# ProPrj_hackpod.net
KiCad netlist of a schematic drawn in EasyEDA Pro
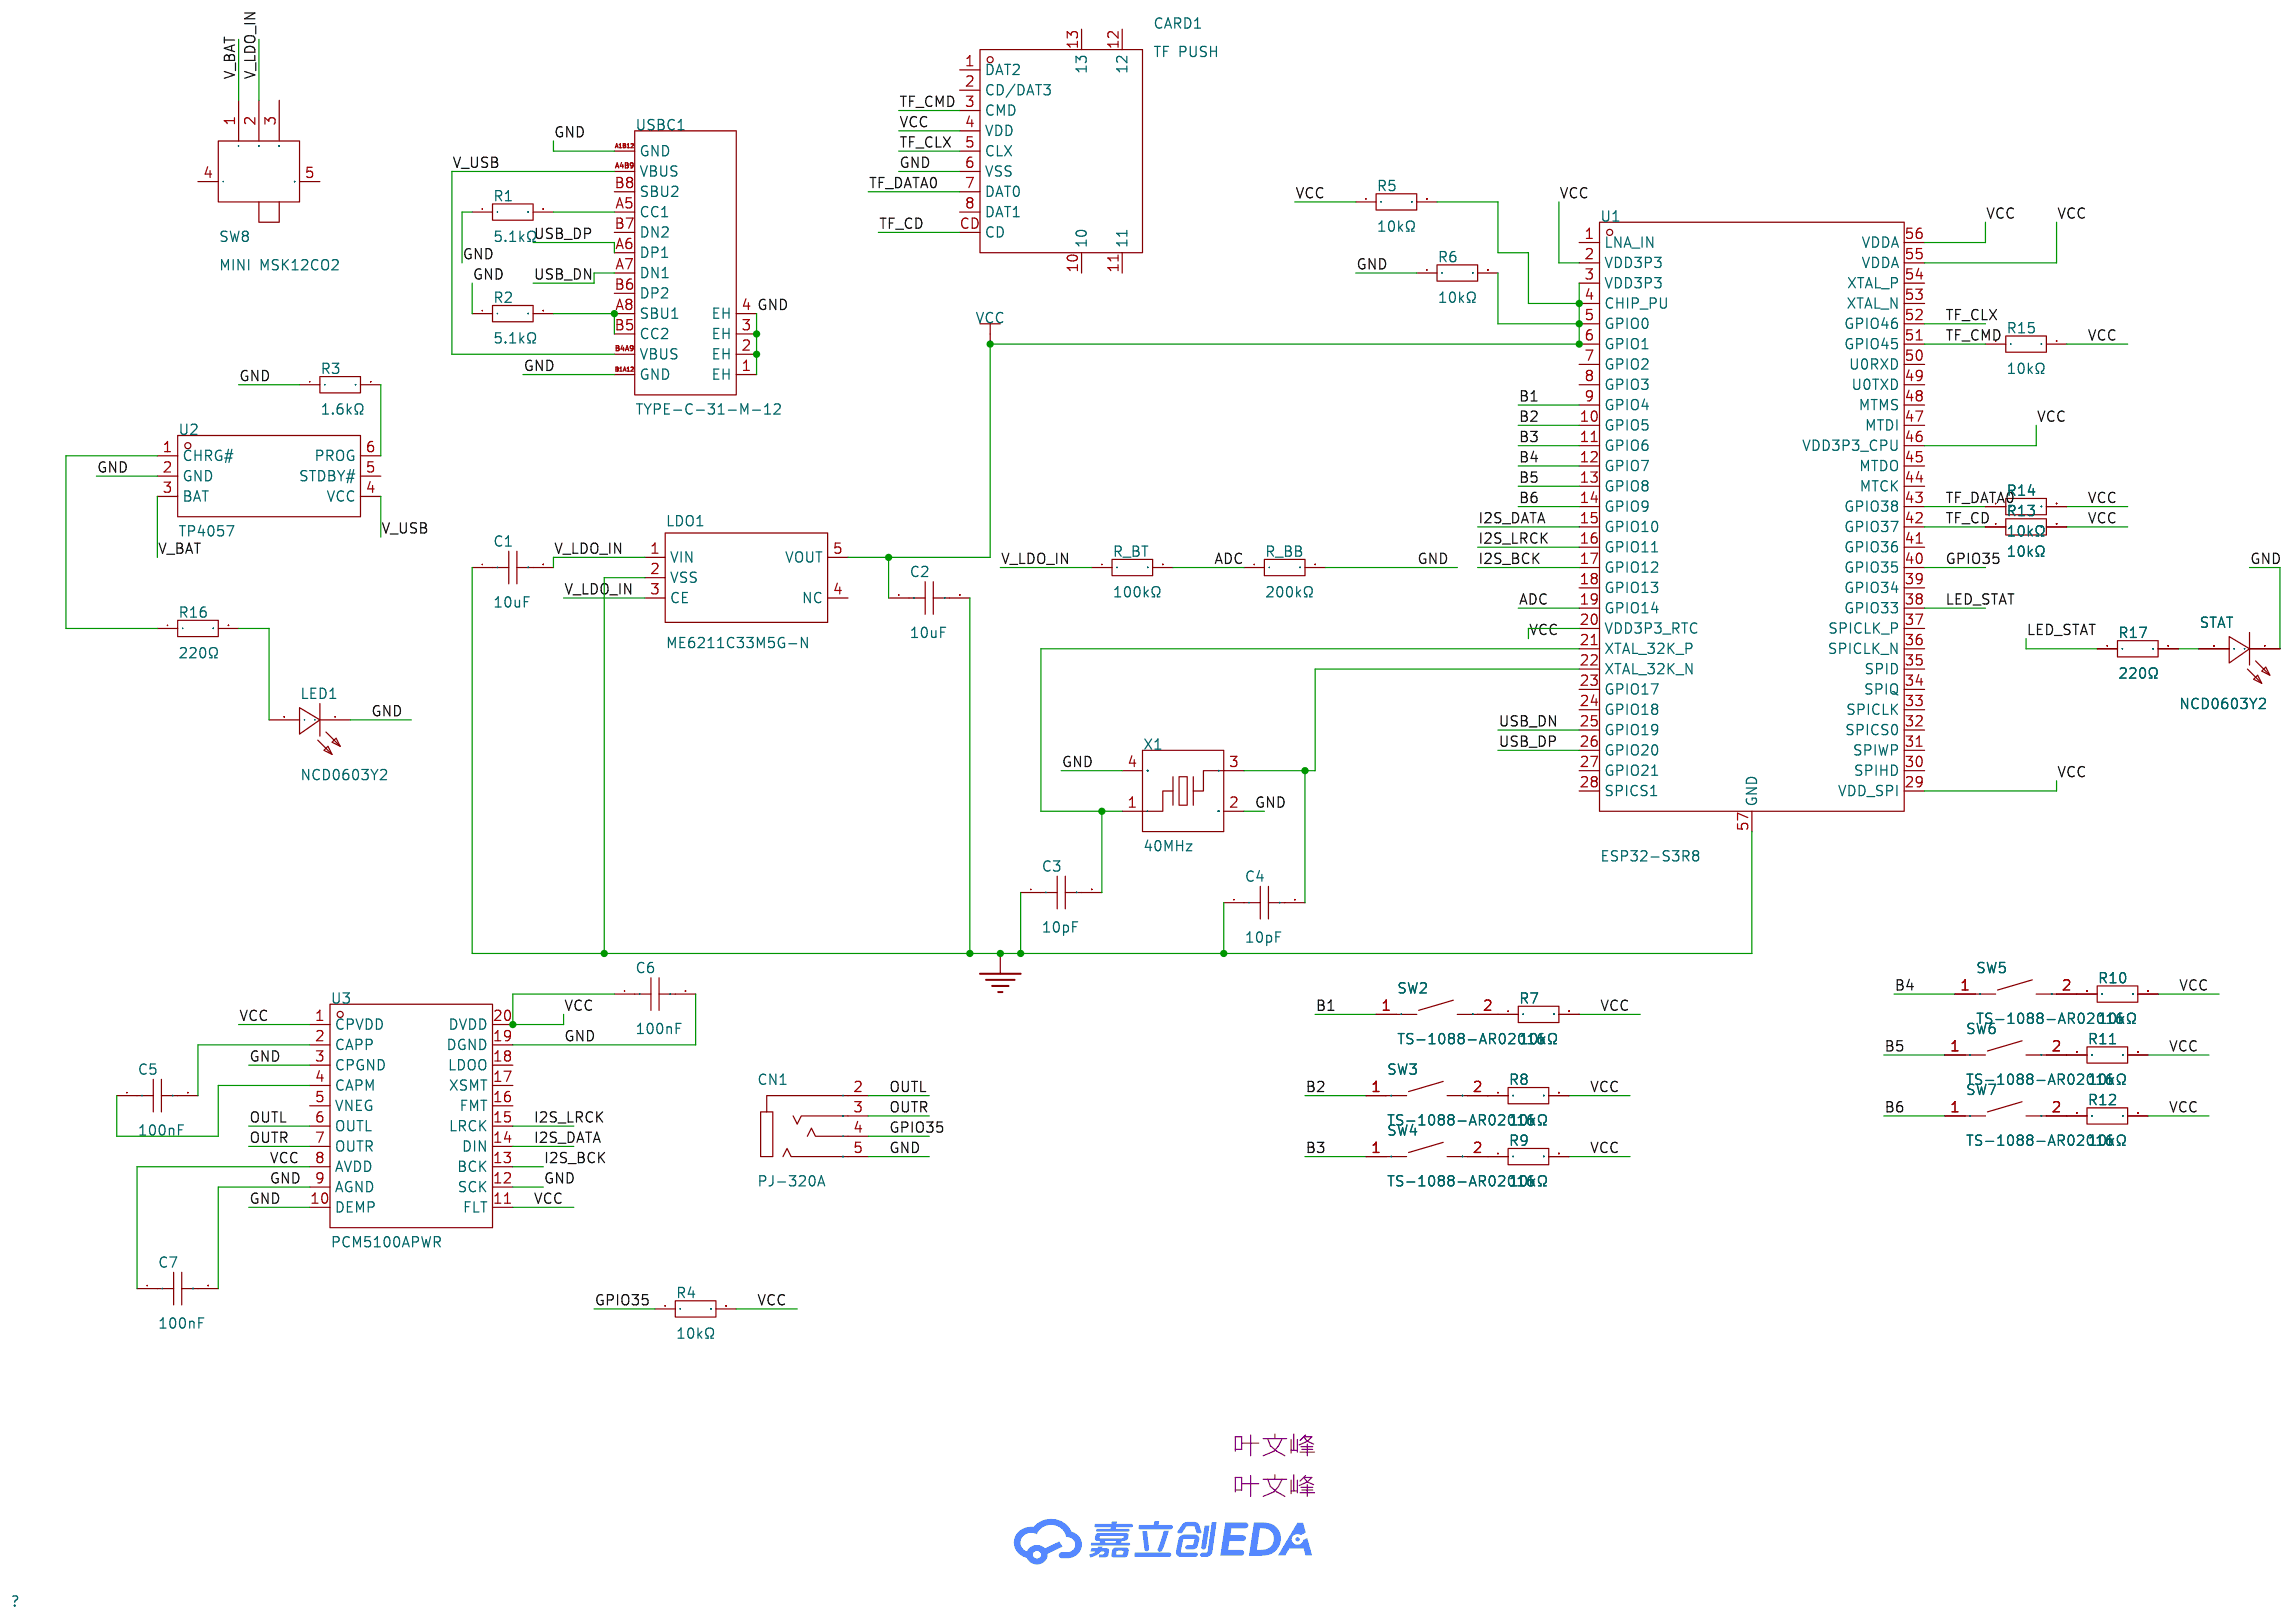
[diagram p0: schematic sheet]

(export (version "E")
  (design (tool "Eeschema 10.0.6"))
  (components
    (comp (ref "C1")
      (value "10uF")
      (footprint "easyedapro:C0603")
      (libsource (lib "easyedapro") (part "Capacitance"))
    )
    (comp (ref "C2")
      (value "10uF")
      (footprint "easyedapro:C0603")
      (libsource (lib "easyedapro") (part "Capacitance"))
    )
    (comp (ref "C3")
      (value "10pF")
      (footprint "easyedapro:C0603")
      (libsource (lib "easyedapro") (part "Capacitance"))
    )
    (comp (ref "C4")
      (value "10pF")
      (footprint "easyedapro:C0603")
      (libsource (lib "easyedapro") (part "Capacitance"))
    )
    (comp (ref "C5")
      (value "100nF")
      (footprint "easyedapro:C0603")
      (libsource (lib "easyedapro") (part "Capacitance"))
    )
    (comp (ref "C6")
      (value "100nF")
      (footprint "easyedapro:C0603")
      (libsource (lib "easyedapro") (part "Capacitance"))
    )
    (comp (ref "C7")
      (value "100nF")
      (footprint "easyedapro:C0603")
      (libsource (lib "easyedapro") (part "Capacitance"))
    )
    (comp (ref "CARD1")
      (value "TF PUSH")
      (footprint "easyedapro:TF-SMD_TF-PUSH")
      (description "卡连接方式:自弹式;卡类型:MicroSD卡(TF卡);连接器类型:卡座;本体最大高度:2mm;工作温度:-25°C~+90°C;")
      (fields (field (name "Manufacturer") "SHOU HAN(首韩)"))
      (libsource (lib "easyedapro") (part "TF PUSH"))
    )
    (comp (ref "CN1")
      (value "PJ-320A")
      (footprint "easyedapro:AUDIO-TH_PJ-320A_C49284721")
      (description "连接器类型:3.5mm耳机座;额定电流:500mA;额定电压:30V;触头材质:铜;触头镀层:金;工作温度:-25°C~+85°C;")
      (fields (field (name "Manufacturer") "XUNPU(讯普)"))
      (libsource (lib "easyedapro") (part "PJ-320A_C49284721"))
    )
    (comp (ref "LDO1")
      (value "ME6211C33M5G-N")
      (footprint "easyedapro:SOT-23-5_L3.0-W1.7-P0.95-LS2.8-BL")
      (description "输出类型:固定;工作电压:6V;输出电压:3.3V;输出电流:500mA;电源纹波抑制比(PSRR):70dB@(1kHz);输出极性:正极;")
      (fields (field (name "Manufacturer") "MICRONE(南京微盟)"))
      (libsource (lib "easyedapro") (part "ME6211C33M5G-N"))
    )
    (comp (ref "LED1")
      (value "NCD0603Y2")
      (footprint "easyedapro:LED0603-RD")
      (fields (field (name "Manufacturer") "国星光电"))
      (libsource (lib "easyedapro") (part "FC-1608YXK-585F08"))
    )
    (comp (ref "R1")
      (value "5.1kΩ")
      (footprint "easyedapro:R0603")
      (libsource (lib "easyedapro") (part "电阻"))
    )
    (comp (ref "R2")
      (value "5.1kΩ")
      (footprint "easyedapro:R0603")
      (libsource (lib "easyedapro") (part "电阻"))
    )
    (comp (ref "R3")
      (value "1.6kΩ")
      (footprint "easyedapro:R0603")
      (libsource (lib "easyedapro") (part "电阻"))
    )
    (comp (ref "R4") (value "10kΩ") (footprint "easyedapro:R0603") (libsource (lib "easyedapro") (part "电阻")))
    (comp (ref "R5") (value "10kΩ") (footprint "easyedapro:R0603") (libsource (lib "easyedapro") (part "电阻")))
    (comp (ref "R6") (value "10kΩ") (footprint "easyedapro:R0603") (libsource (lib "easyedapro") (part "电阻")))
    (comp (ref "R7") (value "10kΩ") (footprint "easyedapro:R0603") (libsource (lib "easyedapro") (part "电阻")))
    (comp (ref "R8") (value "10kΩ") (footprint "easyedapro:R0603") (libsource (lib "easyedapro") (part "电阻")))
    (comp (ref "R9") (value "10kΩ") (footprint "easyedapro:R0603") (libsource (lib "easyedapro") (part "电阻")))
    (comp (ref "R10")
      (value "10kΩ")
      (footprint "easyedapro:R0603")
      (libsource (lib "easyedapro") (part "电阻"))
    )
    (comp (ref "R11")
      (value "10kΩ")
      (footprint "easyedapro:R0603")
      (libsource (lib "easyedapro") (part "电阻"))
    )
    (comp (ref "R12")
      (value "10kΩ")
      (footprint "easyedapro:R0603")
      (libsource (lib "easyedapro") (part "电阻"))
    )
    (comp (ref "R13")
      (value "10kΩ")
      (footprint "easyedapro:R0603")
      (libsource (lib "easyedapro") (part "电阻"))
    )
    (comp (ref "R14")
      (value "10kΩ")
      (footprint "easyedapro:R0603")
      (libsource (lib "easyedapro") (part "电阻"))
    )
    (comp (ref "R15")
      (value "10kΩ")
      (footprint "easyedapro:R0603")
      (libsource (lib "easyedapro") (part "电阻"))
    )
    (comp (ref "R16")
      (value "220Ω")
      (footprint "easyedapro:R0603")
      (libsource (lib "easyedapro") (part "电阻"))
    )
    (comp (ref "R17")
      (value "220Ω")
      (footprint "easyedapro:R0603")
      (fields (field (name "Manufacturer Part") "FRC0603J221 TS") (field (name "Manufacturer") "FOJAN(富捷)"))
      (libsource (lib "easyedapro") (part "电阻"))
    )
    (comp (ref "R_BB")
      (value "200kΩ")
      (footprint "easyedapro:R0603")
      (fields (field (name "Manufacturer Part") "ERA3AEB204V") (field (name "Manufacturer") "PANASONIC(松下)"))
      (libsource (lib "easyedapro") (part "电阻"))
    )
    (comp (ref "R_BT")
      (value "100kΩ")
      (footprint "easyedapro:R0603")
      (fields (field (name "Manufacturer Part") "ERJ3EKF1003V") (field (name "Manufacturer") "PANASONIC(松下)"))
      (libsource (lib "easyedapro") (part "电阻"))
    )
    (comp (ref "STAT")
      (value "NCD0603Y2")
      (footprint "easyedapro:LED0603-RD")
      (fields (field (name "Manufacturer") "国星光电"))
      (libsource (lib "easyedapro") (part "FC-1608YXK-585F08"))
    )
    (comp (ref "SW2")
      (value "TS-1088-AR02016")
      (footprint "easyedapro:SW-SMD_L3.9-W3.0-P4.45")
      (fields (field (name "Manufacturer") "XUNPU(讯普)"))
      (libsource (lib "easyedapro") (part "TS-1088-AR02016"))
    )
    (comp (ref "SW3")
      (value "TS-1088-AR02016")
      (footprint "easyedapro:SW-SMD_L3.9-W3.0-P4.45")
      (fields (field (name "Manufacturer") "XUNPU(讯普)"))
      (libsource (lib "easyedapro") (part "TS-1088-AR02016"))
    )
    (comp (ref "SW4")
      (value "TS-1088-AR02016")
      (footprint "easyedapro:SW-SMD_L3.9-W3.0-P4.45")
      (fields (field (name "Manufacturer") "XUNPU(讯普)"))
      (libsource (lib "easyedapro") (part "TS-1088-AR02016"))
    )
    (comp (ref "SW5")
      (value "TS-1088-AR02016")
      (footprint "easyedapro:SW-SMD_L3.9-W3.0-P4.45")
      (fields (field (name "Manufacturer") "XUNPU(讯普)"))
      (libsource (lib "easyedapro") (part "TS-1088-AR02016"))
    )
    (comp (ref "SW6")
      (value "TS-1088-AR02016")
      (footprint "easyedapro:SW-SMD_L3.9-W3.0-P4.45")
      (fields (field (name "Manufacturer") "XUNPU(讯普)"))
      (libsource (lib "easyedapro") (part "TS-1088-AR02016"))
    )
    (comp (ref "SW7")
      (value "TS-1088-AR02016")
      (footprint "easyedapro:SW-SMD_L3.9-W3.0-P4.45")
      (fields (field (name "Manufacturer") "XUNPU(讯普)"))
      (libsource (lib "easyedapro") (part "TS-1088-AR02016"))
    )
    (comp (ref "SW8")
      (value "MINI MSK12CO2")
      (footprint "easyedapro:SW-SMD_MSK12CO2")
      (description "电路结构:单刀双掷;安装方式:卧贴;开关颜色:白色;额定电流:50mA;额定电压:12V;工作寿命:1万次;")
      (fields (field (name "Manufacturer") "SHOU HAN(首韩)"))
      (libsource (lib "easyedapro") (part "MINI MSK12CO2"))
    )
    (comp (ref "U1")
      (value "ESP32-S3R8")
      (footprint "easyedapro:QFN-56_L7.0-W7.0-P0.40-TL-EP4.0")
      (fields (field (name "Manufacturer") "ESPRESSIF(乐鑫)"))
      (libsource (lib "easyedapro") (part "ESP32-S3(R8)"))
    )
    (comp (ref "U2")
      (value "TP4057")
      (footprint "easyedapro:SOT-23-6_L2.9-W1.6-P0.95-LS2.8-BR")
      (description "工作电压:4V~6.5V;最大充电电流:500mA;电池类型:锂离子;电池节数:1;")
      (fields (field (name "Manufacturer") "UMW(友台半导体)"))
      (libsource (lib "easyedapro") (part "TP4057_C725791"))
    )
    (comp (ref "U3")
      (value "PCM5100APWR")
      (footprint "easyedapro:TSSOP-20_L6.5-W4.4-P0.65-LS6.4-BL")
      (description "工作电压:1.8V~3.3V;接口类型:I2S;")
      (fields (field (name "Manufacturer") "TI(德州仪器)"))
      (libsource (lib "easyedapro") (part "PCM5100APWR"))
    )
    (comp (ref "USBC1")
      (value "TYPE-C-31-M-12")
      (footprint "easyedapro:USB-C_SMD-TYPE-C-31-M-12_1")
      (description "连接器类型:Type-C;协议标准:-;公母:母;安装方式:-;触点数量:16P;端口数量:1;额定电流 - 电源:5A;工作温度:-;")
      (fields (field (name "Manufacturer") "韩国韩荣"))
      (libsource (lib "easyedapro") (part "TYPE-C-31-M-12"))
    )
    (comp (ref "X1")
      (value "40MHz")
      (footprint "easyedapro:CRYSTAL-SMD_4P-L3.2-W2.5-BL")
      (description "晶振类型:贴片晶振;频率:40MHz;常温频差:±10ppm;负载电容:15pF;频率稳定度:±20ppm;")
      (fields
        (field (name "Manufacturer Part") "XL2EL89CPI-111YLC-40M")
        (field (name "Manufacturer") "YXC(扬兴晶振)")
      )
      (libsource (lib "easyedapro") (part "XL2EL89CPI-111YLC-40M"))
    )
  )
  (nets
    (net (code "1") (name "/ADC") (class "Default")
      (node (ref "R_BB") (pin "1") (pinfunction "1_1") (pintype "input"))
      (node (ref "R_BT") (pin "2") (pinfunction "2_2") (pintype "input"))
      (node (ref "U1") (pin "19") (pinfunction "GPIO14_19") (pintype "unspecified"))
    )
    (net (code "2") (name "/B1") (class "Default")
      (node (ref "SW2") (pin "1") (pinfunction "1_1") (pintype "unspecified"))
      (node (ref "U1") (pin "9") (pinfunction "GPIO4_9") (pintype "unspecified"))
    )
    (net (code "3") (name "/B2") (class "Default")
      (node (ref "SW3") (pin "1") (pinfunction "1_1") (pintype "unspecified"))
      (node (ref "U1") (pin "10") (pinfunction "GPIO5_10") (pintype "unspecified"))
    )
    (net (code "4") (name "/B3") (class "Default")
      (node (ref "SW4") (pin "1") (pinfunction "1_1") (pintype "unspecified"))
      (node (ref "U1") (pin "11") (pinfunction "GPIO6_11") (pintype "unspecified"))
    )
    (net (code "5") (name "/B4") (class "Default")
      (node (ref "SW5") (pin "1") (pinfunction "1_1") (pintype "unspecified"))
      (node (ref "U1") (pin "12") (pinfunction "GPIO7_12") (pintype "unspecified"))
    )
    (net (code "6") (name "/B5") (class "Default")
      (node (ref "SW6") (pin "1") (pinfunction "1_1") (pintype "unspecified"))
      (node (ref "U1") (pin "13") (pinfunction "GPIO8_13") (pintype "unspecified"))
    )
    (net (code "7") (name "/B6") (class "Default")
      (node (ref "SW7") (pin "1") (pinfunction "1_1") (pintype "unspecified"))
      (node (ref "U1") (pin "14") (pinfunction "GPIO9_14") (pintype "unspecified"))
    )
    (net (code "8") (name "/GPIO35") (class "Default")
      (node (ref "CN1") (pin "4") (pinfunction "4_4") (pintype "unspecified"))
      (node (ref "R4") (pin "1") (pinfunction "1_1") (pintype "input"))
      (node (ref "U1") (pin "40") (pinfunction "GPIO35_40") (pintype "unspecified"))
    )
    (net (code "9") (name "/I2S_BCK") (class "Default")
      (node (ref "U1") (pin "17") (pinfunction "GPIO12_17") (pintype "unspecified"))
      (node (ref "U3") (pin "13") (pinfunction "BCK_13") (pintype "unspecified"))
    )
    (net (code "10") (name "/I2S_DATA") (class "Default")
      (node (ref "U1") (pin "15") (pinfunction "GPIO10_15") (pintype "unspecified"))
      (node (ref "U3") (pin "14") (pinfunction "DIN_14") (pintype "unspecified"))
    )
    (net (code "11") (name "/I2S_LRCK") (class "Default")
      (node (ref "U1") (pin "16") (pinfunction "GPIO11_16") (pintype "unspecified"))
      (node (ref "U3") (pin "15") (pinfunction "LRCK_15") (pintype "unspecified"))
    )
    (net (code "12") (name "/LED_STAT") (class "Default")
      (node (ref "R17") (pin "1") (pinfunction "1_1") (pintype "input"))
      (node (ref "U1") (pin "38") (pinfunction "GPIO33_38") (pintype "unspecified"))
    )
    (net (code "13") (name "/OUTL") (class "Default")
      (node (ref "CN1") (pin "2") (pinfunction "2_2") (pintype "unspecified"))
      (node (ref "U3") (pin "6") (pinfunction "OUTL_6") (pintype "unspecified"))
    )
    (net (code "14") (name "/OUTR") (class "Default")
      (node (ref "CN1") (pin "3") (pinfunction "3_3") (pintype "unspecified"))
      (node (ref "U3") (pin "7") (pinfunction "OUTR_7") (pintype "unspecified"))
    )
    (net (code "15") (name "/TF_CD") (class "Default")
      (node (ref "CARD1") (pin "CD") (pinfunction "CD_CD") (pintype "unspecified"))
      (node (ref "R13") (pin "1") (pinfunction "1_1") (pintype "input"))
      (node (ref "U1") (pin "42") (pinfunction "GPIO37_42") (pintype "unspecified"))
    )
    (net (code "16") (name "/TF_CLX") (class "Default")
      (node (ref "CARD1") (pin "5") (pinfunction "CLX_5") (pintype "unspecified"))
      (node (ref "U1") (pin "52") (pinfunction "GPIO46_52") (pintype "unspecified"))
    )
    (net (code "17") (name "/TF_CMD") (class "Default")
      (node (ref "CARD1") (pin "3") (pinfunction "CMD_3") (pintype "unspecified"))
      (node (ref "R15") (pin "1") (pinfunction "1_1") (pintype "input"))
      (node (ref "U1") (pin "51") (pinfunction "GPIO45_51") (pintype "unspecified"))
    )
    (net (code "18") (name "/TF_DATA0") (class "Default")
      (node (ref "CARD1") (pin "7") (pinfunction "DAT0_7") (pintype "unspecified"))
      (node (ref "R14") (pin "1") (pinfunction "1_1") (pintype "input"))
      (node (ref "U1") (pin "43") (pinfunction "GPIO38_43") (pintype "unspecified"))
    )
    (net (code "19") (name "/USB_DN") (class "Default")
      (node (ref "U1") (pin "25") (pinfunction "GPIO19_25") (pintype "unspecified"))
      (node (ref "USBC1") (pin "A7") (pinfunction "DN1_A7") (pintype "unspecified"))
    )
    (net (code "20") (name "/USB_DP") (class "Default")
      (node (ref "U1") (pin "26") (pinfunction "GPIO20_26") (pintype "unspecified"))
      (node (ref "USBC1") (pin "A6") (pinfunction "DP1_A6") (pintype "unspecified"))
    )
    (net (code "21") (name "/V_BAT") (class "Default")
      (node (ref "SW8") (pin "1") (pinfunction "1_1") (pintype "unspecified"))
      (node (ref "U2") (pin "3") (pinfunction "BAT_3") (pintype "unspecified"))
    )
    (net (code "22") (name "/V_LDO_IN") (class "Default")
      (node (ref "C1") (pin "2") (pinfunction "2_2") (pintype "input"))
      (node (ref "LDO1") (pin "1") (pinfunction "VIN_1") (pintype "unspecified"))
      (node (ref "LDO1") (pin "3") (pinfunction "CE_3") (pintype "unspecified"))
      (node (ref "R_BT") (pin "1") (pinfunction "1_1") (pintype "input"))
      (node (ref "SW8") (pin "2") (pinfunction "2_2") (pintype "unspecified"))
    )
    (net (code "23") (name "/V_USB") (class "Default")
      (node (ref "U2") (pin "4") (pinfunction "VCC_4") (pintype "unspecified"))
      (node (ref "USBC1") (pin "A4B9") (pinfunction "VBUS_A4B9") (pintype "unspecified"))
      (node (ref "USBC1") (pin "B4A9") (pinfunction "VBUS_B4A9") (pintype "unspecified"))
    )
    (net (code "24") (name "GND") (class "Default")
      (node (ref "C1") (pin "1") (pinfunction "1_1") (pintype "input"))
      (node (ref "C2") (pin "2") (pinfunction "2_2") (pintype "input"))
      (node (ref "C3") (pin "1") (pinfunction "1_1") (pintype "input"))
      (node (ref "C4") (pin "1") (pinfunction "1_1") (pintype "input"))
      (node (ref "C6") (pin "2") (pinfunction "2_2") (pintype "input"))
      (node (ref "C7") (pin "2") (pinfunction "2_2") (pintype "input"))
      (node (ref "CARD1") (pin "6") (pinfunction "VSS_6") (pintype "unspecified"))
      (node (ref "CN1") (pin "5") (pinfunction "5_5") (pintype "unspecified"))
      (node (ref "LDO1") (pin "2") (pinfunction "VSS_2") (pintype "unspecified"))
      (node (ref "LED1") (pin "1") (pinfunction "K_1") (pintype "unspecified"))
      (node (ref "R1") (pin "1") (pinfunction "1_1") (pintype "input"))
      (node (ref "R2") (pin "1") (pinfunction "1_1") (pintype "input"))
      (node (ref "R3") (pin "1") (pinfunction "1_1") (pintype "input"))
      (node (ref "R6") (pin "1") (pinfunction "1_1") (pintype "input"))
      (node (ref "R_BB") (pin "2") (pinfunction "2_2") (pintype "input"))
      (node (ref "STAT") (pin "1") (pinfunction "K_1") (pintype "unspecified"))
      (node (ref "U1") (pin "57") (pinfunction "GND_57") (pintype "unspecified"))
      (node (ref "U2") (pin "2") (pinfunction "GND_2") (pintype "unspecified"))
      (node (ref "U3") (pin "10") (pinfunction "DEMP_10") (pintype "unspecified"))
      (node (ref "U3") (pin "12") (pinfunction "SCK_12") (pintype "unspecified"))
      (node (ref "U3") (pin "19") (pinfunction "DGND_19") (pintype "unspecified"))
      (node (ref "U3") (pin "3") (pinfunction "CPGND_3") (pintype "unspecified"))
      (node (ref "U3") (pin "9") (pinfunction "AGND_9") (pintype "unspecified"))
      (node (ref "USBC1") (pin "1") (pinfunction "EH_1") (pintype "unspecified"))
      (node (ref "USBC1") (pin "2") (pinfunction "EH_2") (pintype "unspecified"))
      (node (ref "USBC1") (pin "3") (pinfunction "EH_3") (pintype "unspecified"))
      (node (ref "USBC1") (pin "4") (pinfunction "EH_4") (pintype "unspecified"))
      (node (ref "USBC1") (pin "A1B12") (pinfunction "GND_A1B12") (pintype "unspecified"))
      (node (ref "USBC1") (pin "B1A12") (pinfunction "GND_B1A12") (pintype "unspecified"))
      (node (ref "X1") (pin "2") (pinfunction "GND_2") (pintype "input"))
      (node (ref "X1") (pin "4") (pinfunction "GND_4") (pintype "input"))
    )
    (net (code "25") (name "Net-(LED1-A)") (class "Default")
      (node (ref "LED1") (pin "2") (pinfunction "A_2") (pintype "unspecified"))
      (node (ref "R16") (pin "2") (pinfunction "2_2") (pintype "input"))
    )
    (net (code "26") (name "Net-(R7-Pad1)") (class "Default")
      (node (ref "R7") (pin "1") (pinfunction "1_1") (pintype "input"))
      (node (ref "SW2") (pin "2") (pinfunction "2_2") (pintype "unspecified"))
    )
    (net (code "27") (name "Net-(R8-Pad1)") (class "Default")
      (node (ref "R8") (pin "1") (pinfunction "1_1") (pintype "input"))
      (node (ref "SW3") (pin "2") (pinfunction "2_2") (pintype "unspecified"))
    )
    (net (code "28") (name "Net-(R9-Pad1)") (class "Default")
      (node (ref "R9") (pin "1") (pinfunction "1_1") (pintype "input"))
      (node (ref "SW4") (pin "2") (pinfunction "2_2") (pintype "unspecified"))
    )
    (net (code "29") (name "Net-(R10-Pad1)") (class "Default")
      (node (ref "R10") (pin "1") (pinfunction "1_1") (pintype "input"))
      (node (ref "SW5") (pin "2") (pinfunction "2_2") (pintype "unspecified"))
    )
    (net (code "30") (name "Net-(R11-Pad1)") (class "Default")
      (node (ref "R11") (pin "1") (pinfunction "1_1") (pintype "input"))
      (node (ref "SW6") (pin "2") (pinfunction "2_2") (pintype "unspecified"))
    )
    (net (code "31") (name "Net-(R12-Pad1)") (class "Default")
      (node (ref "R12") (pin "1") (pinfunction "1_1") (pintype "input"))
      (node (ref "SW7") (pin "2") (pinfunction "2_2") (pintype "unspecified"))
    )
    (net (code "32") (name "Net-(STAT-A)") (class "Default")
      (node (ref "R17") (pin "2") (pinfunction "2_2") (pintype "input"))
      (node (ref "STAT") (pin "2") (pinfunction "A_2") (pintype "unspecified"))
    )
    (net (code "33") (name "Net-(U1-XTAL_32K_N)") (class "Default")
      (node (ref "C4") (pin "2") (pinfunction "2_2") (pintype "input"))
      (node (ref "U1") (pin "22") (pinfunction "XTAL_32K_N_22") (pintype "unspecified"))
      (node (ref "X1") (pin "3") (pinfunction "3_3") (pintype "input"))
    )
    (net (code "34") (name "Net-(U1-XTAL_32K_P)") (class "Default")
      (node (ref "C3") (pin "2") (pinfunction "2_2") (pintype "input"))
      (node (ref "U1") (pin "21") (pinfunction "XTAL_32K_P_21") (pintype "unspecified"))
      (node (ref "X1") (pin "1") (pinfunction "1_1") (pintype "input"))
    )
    (net (code "35") (name "Net-(U2-CHRG#)") (class "Default")
      (node (ref "R16") (pin "1") (pinfunction "1_1") (pintype "input"))
      (node (ref "U2") (pin "1") (pinfunction "CHRG#_1") (pintype "unspecified"))
    )
    (net (code "36") (name "Net-(U2-PROG)") (class "Default")
      (node (ref "R3") (pin "2") (pinfunction "2_2") (pintype "input"))
      (node (ref "U2") (pin "6") (pinfunction "PROG_6") (pintype "unspecified"))
    )
    (net (code "37") (name "Net-(U3-CAPM)") (class "Default")
      (node (ref "C5") (pin "1") (pinfunction "1_1") (pintype "input"))
      (node (ref "U3") (pin "4") (pinfunction "CAPM_4") (pintype "unspecified"))
    )
    (net (code "38") (name "Net-(U3-CAPP)") (class "Default")
      (node (ref "C5") (pin "2") (pinfunction "2_2") (pintype "input"))
      (node (ref "U3") (pin "2") (pinfunction "CAPP_2") (pintype "unspecified"))
    )
    (net (code "39") (name "Net-(USBC1-CC1)") (class "Default")
      (node (ref "R1") (pin "2") (pinfunction "2_2") (pintype "input"))
      (node (ref "USBC1") (pin "A5") (pinfunction "CC1_A5") (pintype "unspecified"))
    )
    (net (code "40") (name "Net-(USBC1-CC2)") (class "Default")
      (node (ref "R2") (pin "2") (pinfunction "2_2") (pintype "input"))
      (node (ref "USBC1") (pin "A8") (pinfunction "SBU1_A8") (pintype "unspecified"))
      (node (ref "USBC1") (pin "B5") (pinfunction "CC2_B5") (pintype "unspecified"))
    )
    (net (code "41") (name "VCC") (class "Default")
      (node (ref "C2") (pin "1") (pinfunction "1_1") (pintype "input"))
      (node (ref "C6") (pin "1") (pinfunction "1_1") (pintype "input"))
      (node (ref "C7") (pin "1") (pinfunction "1_1") (pintype "input"))
      (node (ref "CARD1") (pin "4") (pinfunction "VDD_4") (pintype "unspecified"))
      (node (ref "LDO1") (pin "5") (pinfunction "VOUT_5") (pintype "unspecified"))
      (node (ref "R10") (pin "2") (pinfunction "2_2") (pintype "input"))
      (node (ref "R11") (pin "2") (pinfunction "2_2") (pintype "input"))
      (node (ref "R12") (pin "2") (pinfunction "2_2") (pintype "input"))
      (node (ref "R13") (pin "2") (pinfunction "2_2") (pintype "input"))
      (node (ref "R14") (pin "2") (pinfunction "2_2") (pintype "input"))
      (node (ref "R15") (pin "2") (pinfunction "2_2") (pintype "input"))
      (node (ref "R4") (pin "2") (pinfunction "2_2") (pintype "input"))
      (node (ref "R5") (pin "1") (pinfunction "1_1") (pintype "input"))
      (node (ref "R5") (pin "2") (pinfunction "2_2") (pintype "input"))
      (node (ref "R6") (pin "2") (pinfunction "2_2") (pintype "input"))
      (node (ref "R7") (pin "2") (pinfunction "2_2") (pintype "input"))
      (node (ref "R8") (pin "2") (pinfunction "2_2") (pintype "input"))
      (node (ref "R9") (pin "2") (pinfunction "2_2") (pintype "input"))
      (node (ref "U1") (pin "2") (pinfunction "VDD3P3_2") (pintype "unspecified"))
      (node (ref "U1") (pin "20") (pinfunction "VDD3P3_RTC_20") (pintype "unspecified"))
      (node (ref "U1") (pin "29") (pinfunction "VDD_SPI_29") (pintype "unspecified"))
      (node (ref "U1") (pin "3") (pinfunction "VDD3P3_3") (pintype "unspecified"))
      (node (ref "U1") (pin "4") (pinfunction "CHIP_PU_4") (pintype "unspecified"))
      (node (ref "U1") (pin "46") (pinfunction "VDD3P3_CPU_46") (pintype "unspecified"))
      (node (ref "U1") (pin "5") (pinfunction "GPIO0_5") (pintype "unspecified"))
      (node (ref "U1") (pin "55") (pinfunction "VDDA_55") (pintype "unspecified"))
      (node (ref "U1") (pin "56") (pinfunction "VDDA_56") (pintype "unspecified"))
      (node (ref "U1") (pin "6") (pinfunction "GPIO1_6") (pintype "unspecified"))
      (node (ref "U3") (pin "1") (pinfunction "CPVDD_1") (pintype "unspecified"))
      (node (ref "U3") (pin "11") (pinfunction "FLT_11") (pintype "unspecified"))
      (node (ref "U3") (pin "20") (pinfunction "DVDD_20") (pintype "unspecified"))
      (node (ref "U3") (pin "8") (pinfunction "AVDD_8") (pintype "unspecified"))
    )
    (net (code "42") (name "unconnected-(CARD1-CD{slash}DAT3-Pad2)") (class "Default")
      (node (ref "CARD1") (pin "2") (pinfunction "CD/DAT3_2") (pintype "unspecified"))
    )
    (net (code "43") (name "unconnected-(CARD1-DAT1-Pad8)") (class "Default")
      (node (ref "CARD1") (pin "8") (pinfunction "DAT1_8") (pintype "unspecified"))
    )
    (net (code "44") (name "unconnected-(CARD1-DAT2-Pad1)") (class "Default")
      (node (ref "CARD1") (pin "1") (pinfunction "DAT2_1") (pintype "unspecified"))
    )
    (net (code "45") (name "unconnected-(CARD1-Pad10)") (class "Default")
      (node (ref "CARD1") (pin "10") (pinfunction "10_10") (pintype "unspecified"))
    )
    (net (code "46") (name "unconnected-(CARD1-Pad11)") (class "Default")
      (node (ref "CARD1") (pin "11") (pinfunction "11_11") (pintype "unspecified"))
    )
    (net (code "47") (name "unconnected-(CARD1-Pad12)") (class "Default")
      (node (ref "CARD1") (pin "12") (pinfunction "12_12") (pintype "unspecified"))
    )
    (net (code "48") (name "unconnected-(CARD1-Pad13)") (class "Default")
      (node (ref "CARD1") (pin "13") (pinfunction "13_13") (pintype "unspecified"))
    )
    (net (code "49") (name "unconnected-(LDO1-NC-Pad4)") (class "Default")
      (node (ref "LDO1") (pin "4") (pinfunction "NC_4") (pintype "unspecified"))
    )
    (net (code "50") (name "unconnected-(SW8-Pad3)") (class "Default")
      (node (ref "SW8") (pin "3") (pinfunction "3_3") (pintype "unspecified"))
    )
    (net (code "51") (name "unconnected-(SW8-Pad4)") (class "Default")
      (node (ref "SW8") (pin "4") (pinfunction "4_4") (pintype "unspecified"))
    )
    (net (code "52") (name "unconnected-(SW8-Pad5)") (class "Default")
      (node (ref "SW8") (pin "5") (pinfunction "5_5") (pintype "unspecified"))
    )
    (net (code "53") (name "unconnected-(U1-GPIO2-Pad7)") (class "Default")
      (node (ref "U1") (pin "7") (pinfunction "GPIO2_7") (pintype "unspecified"))
    )
    (net (code "54") (name "unconnected-(U1-GPIO3-Pad8)") (class "Default")
      (node (ref "U1") (pin "8") (pinfunction "GPIO3_8") (pintype "unspecified"))
    )
    (net (code "55") (name "unconnected-(U1-GPIO13-Pad18)") (class "Default")
      (node (ref "U1") (pin "18") (pinfunction "GPIO13_18") (pintype "unspecified"))
    )
    (net (code "56") (name "unconnected-(U1-GPIO17-Pad23)") (class "Default")
      (node (ref "U1") (pin "23") (pinfunction "GPIO17_23") (pintype "unspecified"))
    )
    (net (code "57") (name "unconnected-(U1-GPIO18-Pad24)") (class "Default")
      (node (ref "U1") (pin "24") (pinfunction "GPIO18_24") (pintype "unspecified"))
    )
    (net (code "58") (name "unconnected-(U1-GPIO21-Pad27)") (class "Default")
      (node (ref "U1") (pin "27") (pinfunction "GPIO21_27") (pintype "unspecified"))
    )
    (net (code "59") (name "unconnected-(U1-GPIO34-Pad39)") (class "Default")
      (node (ref "U1") (pin "39") (pinfunction "GPIO34_39") (pintype "unspecified"))
    )
    (net (code "60") (name "unconnected-(U1-GPIO36-Pad41)") (class "Default")
      (node (ref "U1") (pin "41") (pinfunction "GPIO36_41") (pintype "unspecified"))
    )
    (net (code "61") (name "unconnected-(U1-LNA_IN-Pad1)") (class "Default")
      (node (ref "U1") (pin "1") (pinfunction "LNA_IN_1") (pintype "unspecified"))
    )
    (net (code "62") (name "unconnected-(U1-MTCK-Pad44)") (class "Default")
      (node (ref "U1") (pin "44") (pinfunction "MTCK_44") (pintype "unspecified"))
    )
    (net (code "63") (name "unconnected-(U1-MTDI-Pad47)") (class "Default")
      (node (ref "U1") (pin "47") (pinfunction "MTDI_47") (pintype "unspecified"))
    )
    (net (code "64") (name "unconnected-(U1-MTDO-Pad45)") (class "Default")
      (node (ref "U1") (pin "45") (pinfunction "MTDO_45") (pintype "unspecified"))
    )
    (net (code "65") (name "unconnected-(U1-MTMS-Pad48)") (class "Default")
      (node (ref "U1") (pin "48") (pinfunction "MTMS_48") (pintype "unspecified"))
    )
    (net (code "66") (name "unconnected-(U1-SPICLK-Pad33)") (class "Default")
      (node (ref "U1") (pin "33") (pinfunction "SPICLK_33") (pintype "unspecified"))
    )
    (net (code "67") (name "unconnected-(U1-SPICLK_N-Pad36)") (class "Default")
      (node (ref "U1") (pin "36") (pinfunction "SPICLK_N_36") (pintype "unspecified"))
    )
    (net (code "68") (name "unconnected-(U1-SPICLK_P-Pad37)") (class "Default")
      (node (ref "U1") (pin "37") (pinfunction "SPICLK_P_37") (pintype "unspecified"))
    )
    (net (code "69") (name "unconnected-(U1-SPICS0-Pad32)") (class "Default")
      (node (ref "U1") (pin "32") (pinfunction "SPICS0_32") (pintype "unspecified"))
    )
    (net (code "70") (name "unconnected-(U1-SPICS1-Pad28)") (class "Default")
      (node (ref "U1") (pin "28") (pinfunction "SPICS1_28") (pintype "unspecified"))
    )
    (net (code "71") (name "unconnected-(U1-SPID-Pad35)") (class "Default")
      (node (ref "U1") (pin "35") (pinfunction "SPID_35") (pintype "unspecified"))
    )
    (net (code "72") (name "unconnected-(U1-SPIHD-Pad30)") (class "Default")
      (node (ref "U1") (pin "30") (pinfunction "SPIHD_30") (pintype "unspecified"))
    )
    (net (code "73") (name "unconnected-(U1-SPIQ-Pad34)") (class "Default")
      (node (ref "U1") (pin "34") (pinfunction "SPIQ_34") (pintype "unspecified"))
    )
    (net (code "74") (name "unconnected-(U1-SPIWP-Pad31)") (class "Default")
      (node (ref "U1") (pin "31") (pinfunction "SPIWP_31") (pintype "unspecified"))
    )
    (net (code "75") (name "unconnected-(U1-U0RXD-Pad50)") (class "Default")
      (node (ref "U1") (pin "50") (pinfunction "U0RXD_50") (pintype "unspecified"))
    )
    (net (code "76") (name "unconnected-(U1-U0TXD-Pad49)") (class "Default")
      (node (ref "U1") (pin "49") (pinfunction "U0TXD_49") (pintype "unspecified"))
    )
    (net (code "77") (name "unconnected-(U1-XTAL_N-Pad53)") (class "Default")
      (node (ref "U1") (pin "53") (pinfunction "XTAL_N_53") (pintype "unspecified"))
    )
    (net (code "78") (name "unconnected-(U1-XTAL_P-Pad54)") (class "Default")
      (node (ref "U1") (pin "54") (pinfunction "XTAL_P_54") (pintype "unspecified"))
    )
    (net (code "79") (name "unconnected-(U2-STDBY#-Pad5)") (class "Default")
      (node (ref "U2") (pin "5") (pinfunction "STDBY#_5") (pintype "unspecified"))
    )
    (net (code "80") (name "unconnected-(U3-FMT-Pad16)") (class "Default")
      (node (ref "U3") (pin "16") (pinfunction "FMT_16") (pintype "unspecified"))
    )
    (net (code "81") (name "unconnected-(U3-LDOO-Pad18)") (class "Default")
      (node (ref "U3") (pin "18") (pinfunction "LDOO_18") (pintype "unspecified"))
    )
    (net (code "82") (name "unconnected-(U3-VNEG-Pad5)") (class "Default")
      (node (ref "U3") (pin "5") (pinfunction "VNEG_5") (pintype "unspecified"))
    )
    (net (code "83") (name "unconnected-(U3-XSMT-Pad17)") (class "Default")
      (node (ref "U3") (pin "17") (pinfunction "XSMT_17") (pintype "unspecified"))
    )
    (net (code "84") (name "unconnected-(USBC1-DN2-PadB7)") (class "Default")
      (node (ref "USBC1") (pin "B7") (pinfunction "DN2_B7") (pintype "unspecified"))
    )
    (net (code "85") (name "unconnected-(USBC1-DP2-PadB6)") (class "Default")
      (node (ref "USBC1") (pin "B6") (pinfunction "DP2_B6") (pintype "unspecified"))
    )
    (net (code "86") (name "unconnected-(USBC1-SBU2-PadB8)") (class "Default")
      (node (ref "USBC1") (pin "B8") (pinfunction "SBU2_B8") (pintype "unspecified"))
    )
  )
)
